# STM32F103C8T6_custom-board.net
KiCad netlist of a schematic drawn in Altium Designer
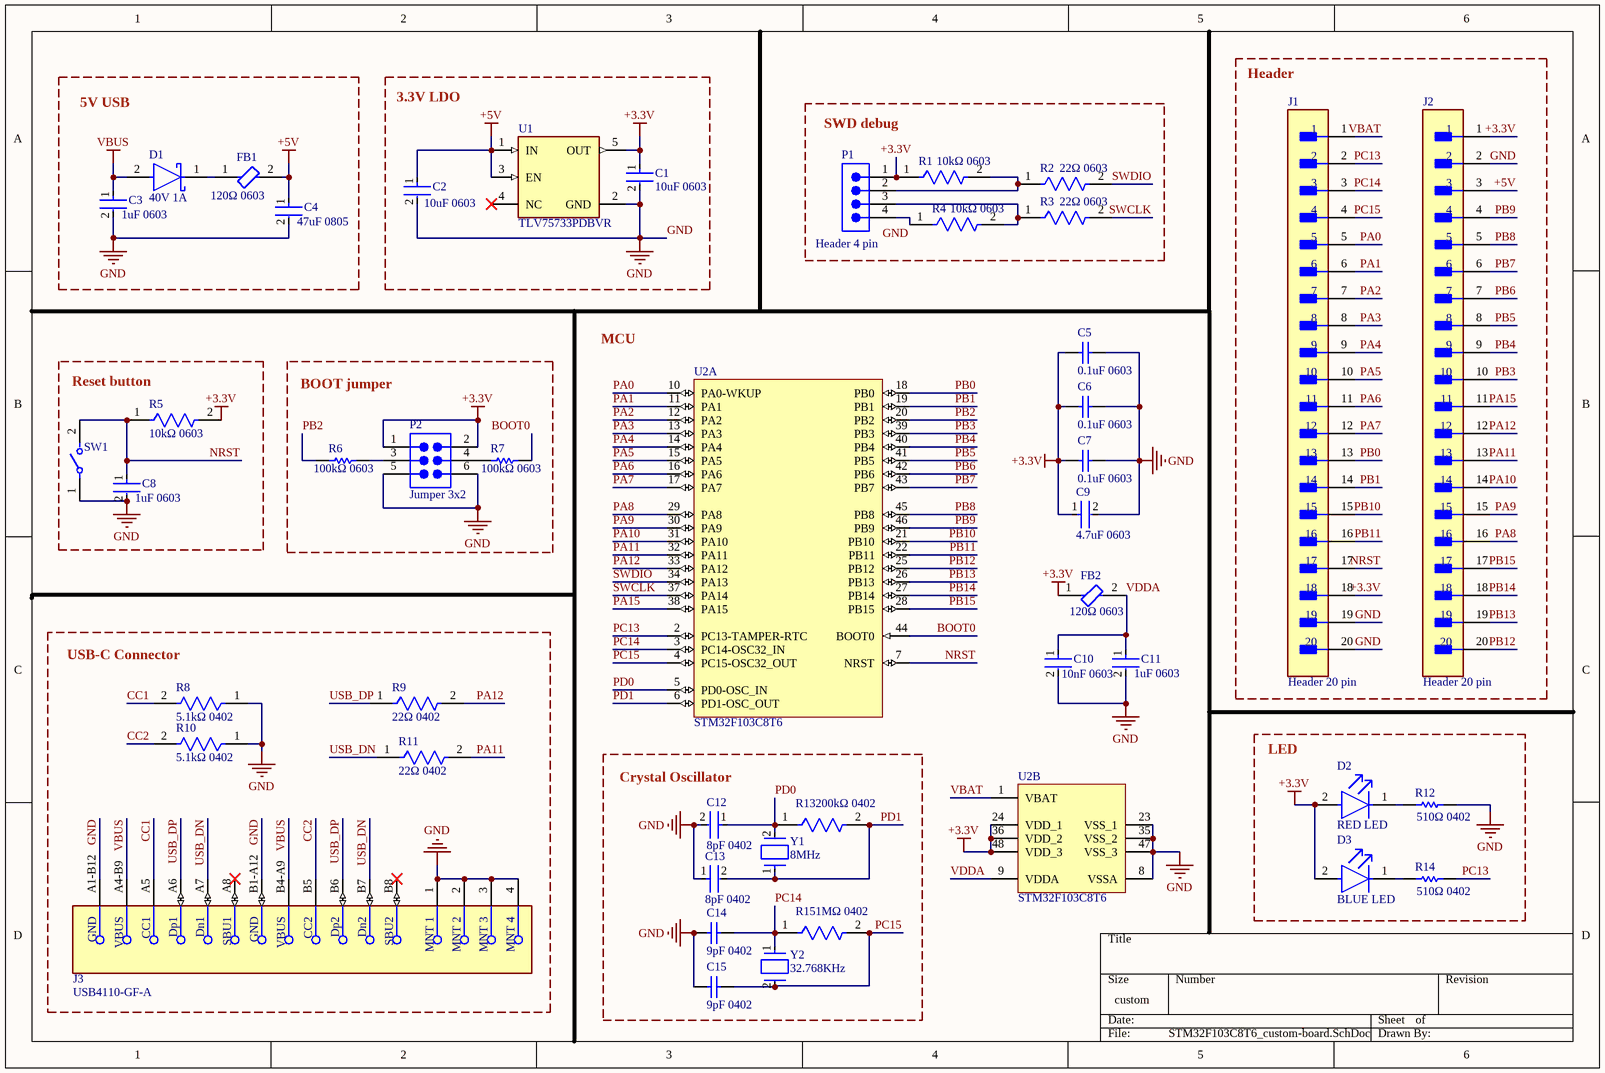
[diagram p0: STM32F103C8T6_custom-board.SchDoc]

(export (version "E")
  (design (tool "Eeschema 10.0.6"))
  (components
    (comp (ref "C1")
      (value "10uF 0603")
      (footprint "FP-CC0603-DC-IPC_A")
      (description "CAP CER 10UF 10V X5R 0603")
      (fields (field (name "TOLERANCE") "10%"))
      (libsource (lib "Altium Content Vault") (part "b4654b650e69147ec39a6b967a45e02"))
    )
    (comp (ref "C2")
      (value "10uF 0603")
      (footprint "FP-CC0603-DC-IPC_A")
      (description "CAP CER 10UF 10V X5R 0603")
      (fields (field (name "TOLERANCE") "10%"))
      (libsource (lib "Altium Content Vault") (part "b4654b650e69147ec39a6b967a45e02"))
    )
    (comp (ref "C3")
      (value "1uF 0603")
      (footprint "FP-VJ0603Y105KXJCW1BC-MFG")
      (description "VJ0603Y105KXJCW1BC Multilayer Ceramic Capacitor, 1 uF, 16 V, ± 10%, X7R, 0603 [1608 Metric]")
      (fields (field (name "TOLERANCE") "10%"))
      (libsource (lib "Altium Content Vault") (part "b4654b650e69147ec39a6b967a45e02"))
    )
    (comp (ref "C4")
      (value "47uF 0805")
      (footprint "FP-C2012-125-0_2-IPC_A")
      (description "Multilayer Ceramic Capacitors 47μF ±20% 10V JB SMD 0805")
      (fields (field (name "TOLERANCE") "20%"))
      (libsource (lib "Altium Content Vault") (part "b4654b650e69147ec39a6b967a45e02"))
    )
    (comp (ref "C5")
      (value "0.1uF 0603")
      (footprint "CAPC1608X95X40ML15T15")
      (fields (field (name "MANUFACTURER") "Vitramon") (field (name "PART NUMBER") "VJ0603Y104KXQCW1BC"))
      (libsource (lib "Altium Content Vault") (part "CAP"))
    )
    (comp (ref "C6")
      (value "0.1uF 0603")
      (footprint "CAPC1608X95X40ML15T15")
      (fields (field (name "MANUFACTURER") "Vitramon") (field (name "PART NUMBER") "VJ0603Y104KXQCW1BC"))
      (libsource (lib "Altium Content Vault") (part "CAP"))
    )
    (comp (ref "C7")
      (value "0.1uF 0603")
      (footprint "CAPC1608X95X40ML15T15")
      (fields (field (name "MANUFACTURER") "Vitramon") (field (name "PART NUMBER") "VJ0603Y104KXQCW1BC"))
      (libsource (lib "Altium Content Vault") (part "CAP"))
    )
    (comp (ref "C8")
      (value "1uF 0603")
      (footprint "FP-VJ0603Y105KXJCW1BC-MFG")
      (description "VJ0603Y105KXJCW1BC Multilayer Ceramic Capacitor, 1 uF, 16 V, ± 10%, X7R, 0603 [1608 Metric]")
      (fields (field (name "TOLERANCE") "10%"))
      (libsource (lib "Altium Content Vault") (part "b4654b650e69147ec39a6b967a45e02"))
    )
    (comp (ref "C9")
      (value "4.7uF 0603")
      (footprint "FP-CC0603-DC-MFG")
      (description "CAP CER 4.7UF 6.3V X7R 0603")
      (fields (field (name "TOLERANCE") "20%"))
      (libsource (lib "Altium Content Vault") (part "11868f565c42a9108669ba33697ecf6"))
    )
    (comp (ref "C10")
      (value "10nF 0603")
      (footprint "FP-C0603C-CF-MFG")
      (description "C0603 10,000 pF X7R 30ppm/°C 5.00% 16 V")
      (fields
        (field (name "MANUFACTURER") "KEMET")
        (field (name "MANUFACTURER PART NUMBER") "C0603C103J4RACAUTO")
      )
      (libsource (lib "Altium Content Vault") (part "b4654b650e69147ec39a6b967a45e02"))
    )
    (comp (ref "C11")
      (value "1uF 0603")
      (footprint "FP-VJ0603Y105KXJCW1BC-MFG")
      (description "VJ0603Y105KXJCW1BC Multilayer Ceramic Capacitor, 1 uF, 16 V, ± 10%, X7R, 0603 [1608 Metric]")
      (fields (field (name "TOLERANCE") "10%"))
      (libsource (lib "Altium Content Vault") (part "b4654b650e69147ec39a6b967a45e02"))
    )
    (comp (ref "C12")
      (value "8pF 0402")
      (footprint "FP-C0402-BB-MFG")
      (description "C0402 8.2 pF C0G 0.5 pF 50 V")
      (fields
        (field (name "OCTOPART") "https://octopart.com/c0402c829d5gacauto-kemet-89441553")
        (field (name "TOLERANCE") "0.5 pF")
      )
      (libsource (lib "Altium Content Vault") (part "b4654b650e69147ec39a6b967a45e02"))
    )
    (comp (ref "C13")
      (value "8pF 0402")
      (footprint "FP-C0402-BB-MFG")
      (description "C0402 8.2 pF C0G 0.5 pF 50 V")
      (fields
        (field (name "OCTOPART") "https://octopart.com/c0402c829d5gacauto-kemet-89441553")
        (field (name "TOLERANCE") "0.5 pF")
      )
      (libsource (lib "Altium Content Vault") (part "b4654b650e69147ec39a6b967a45e02"))
    )
    (comp (ref "C14")
      (value "9pF 0402")
      (footprint "CAPC1005X56X25NL10T15")
      (fields
        (field (name "MANUFACTURER") "AVX Interconnect / Elco")
        (field (name "PART NUMBER") "04023A100DAT2A")
      )
      (libsource (lib "Altium Content Vault") (part "CAP"))
    )
    (comp (ref "C15")
      (value "9pF 0402")
      (footprint "CAPC1005X56X25NL10T15")
      (fields
        (field (name "MANUFACTURER") "AVX Interconnect / Elco")
        (field (name "PART NUMBER") "04023A100DAT2A")
      )
      (libsource (lib "Altium Content Vault") (part "CAP"))
    )
    (comp (ref "D1")
      (value "40V 1A")
      (footprint "FP-SOD123-IPC_A")
      (description "DIODE SCHOTTKY 40V 1A SOD123")
      (libsource (lib "Altium Content Vault") (part "1d6ec82d83fb6aee721767c19dac4b9"))
    )
    (comp (ref "D2")
      (value "RED LED")
      (footprint "FP-SML-LX0603IW-TR-MFG")
      (description "LED RED DIFFUSED SMD")
      (libsource (lib "Altium Content Vault") (part "8706943c75ba83719d021d2fdc84c58"))
    )
    (comp (ref "D3")
      (value "BLUE LED")
      (footprint "FP-LTST-C191TBKT-MFG")
      (description "LED BLUE CLEAR CHIP SMD")
      (libsource (lib "Altium Content Vault") (part "8706943c75ba83719d021d2fdc84c58"))
    )
    (comp (ref "FB1")
      (value "120Ω 0603")
      (footprint "FP-BLM18-0_15-t0_8-MFG")
      (description "Chip Ferrite Bead, 0603, 120Ω @ 100MHz, 0.05Ω, 25%, 2A")
      (libsource (lib "Altium Content Vault") (part "5f30dd21d616792df468990f7003faa"))
    )
    (comp (ref "FB2")
      (value "120Ω 0603")
      (footprint "FP-BLM18-0_15-t0_8-MFG")
      (description "Chip Ferrite Bead, 0603, 120Ω @ 100MHz, 0.05Ω, 25%, 2A")
      (libsource (lib "Altium Content Vault") (part "5f30dd21d616792df468990f7003faa"))
    )
    (comp (ref "J1")
      (value "Header 20 pin")
      (footprint "FP-TSW-120-05-G-S-MFG")
      (description "TSW-120-05-G-S Headers & Wire Housings Classic PCB Header Strips, 0.100 pitch")
      (libsource (lib "Altium Content Vault") (part "aa9a6f52efaac70338c2092749629fc"))
    )
    (comp (ref "J2")
      (value "Header 20 pin")
      (footprint "FP-TSW-120-05-G-S-MFG")
      (description "TSW-120-05-G-S Headers & Wire Housings Classic PCB Header Strips, 0.100 pitch")
      (libsource (lib "Altium Content Vault") (part "aa9a6f52efaac70338c2092749629fc"))
    )
    (comp (ref "J3")
      (value "USB4110-GF-A")
      (footprint "FP-USB4110-GF-A-MFG")
      (description "CONN USB 2.0 TYPE-C R/A SMT")
      (fields
        (field (name "OCTOPART") "https://octopart.com/usb4110-gf-a-gct-103941985")
        (field (name "MANUFACTURER") "GCT")
      )
      (libsource (lib "Altium Content Vault") (part "e23f2b38bb3c3f98e683ebab9ede730"))
    )
    (comp (ref "P1")
      (value "Header 4 pin")
      (footprint "SMTC-TSW-104-08-X-S")
      (description "0.025\" SQ Post Header, Through-hole, Vertical, -55 to 125 degC, 2.54 mm Pitch, 4-Pin, Male, RoHS")
      (fields (field (name "MANUFACTURER") "Samtec") (field (name "PARTNUMBER") "TSW-104-08-G-S"))
      (libsource (lib "Altium Content Vault") (part "SMTC-TSW-104-08-X-S"))
    )
    (comp (ref "P2")
      (value "Jumper 3x2")
      (footprint "SMTC-TSW-103-08-X-D")
      (description "0.025\" SQ Post Header, Through-hole, Vertical, -55 to 125 degC, 2.54 mm Pitch, 6-Pin, Male, RoHS")
      (fields (field (name "MANUFACTURER") "Samtec") (field (name "PARTNUMBER") "TSW-103-08-F-D"))
      (libsource (lib "Altium Content Vault") (part "SMTC-TSW-103-08-X-D"))
    )
    (comp (ref "R1")
      (value "10kΩ 0603")
      (footprint "FP-AC0603-IPC_A")
      (description "RES 10kΩ 5.00% 0.2W 0603")
      (libsource (lib "Altium Content Vault") (part "1029c3af85768c4190bb7ad29bc67b5"))
    )
    (comp (ref "R2")
      (value "22Ω 0603")
      (footprint "FP-RMCF0603-IPC_A")
      (description "22Ω ±5% 0.1W 0603 Thick Film Chip Resistor AEC-Q200 compliant")
      (fields (field (name "TOLERANCE") "5%"))
      (libsource (lib "Altium Content Vault") (part "1029c3af85768c4190bb7ad29bc67b5"))
    )
    (comp (ref "R3")
      (value "22Ω 0603")
      (footprint "FP-RMCF0603-IPC_A")
      (description "22Ω ±5% 0.1W 0603 Thick Film Chip Resistor AEC-Q200 compliant")
      (fields (field (name "TOLERANCE") "5%"))
      (libsource (lib "Altium Content Vault") (part "1029c3af85768c4190bb7ad29bc67b5"))
    )
    (comp (ref "R4")
      (value "10kΩ 0603")
      (footprint "FP-AC0603-IPC_A")
      (description "RES 10kΩ 5.00% 0.2W 0603")
      (libsource (lib "Altium Content Vault") (part "1029c3af85768c4190bb7ad29bc67b5"))
    )
    (comp (ref "R5")
      (value "10kΩ 0603")
      (footprint "FP-AC0603-IPC_A")
      (description "RES 10kΩ 5.00% 0.2W 0603")
      (libsource (lib "Altium Content Vault") (part "1029c3af85768c4190bb7ad29bc67b5"))
    )
    (comp (ref "R6")
      (value "100kΩ 0603")
      (footprint "RESC0603(1608)_N")
      (description "100K 0.1W 1% 0603 (1608 Metric)  SMD")
      (fields (field (name "POWER") "0.1 W") (field (name "TOLERANCE") "1 %"))
      (libsource (lib "Altium Content Vault") (part "RES"))
    )
    (comp (ref "R7")
      (value "100kΩ 0603")
      (footprint "RESC0603(1608)_N")
      (description "100K 0.1W 1% 0603 (1608 Metric)  SMD")
      (fields (field (name "POWER") "0.1 W") (field (name "TOLERANCE") "1 %"))
      (libsource (lib "Altium Content Vault") (part "RES"))
    )
    (comp (ref "R8")
      (value "5.1kΩ 0402")
      (footprint "FP-RN73R1E-IPC_C")
      (description "5.1kΩ ±1% 0.063W, 1/16W Chip Resistor 0402 (1005 Metric) Moisture Resistant Thin Film")
      (libsource (lib "Altium Content Vault") (part "1029c3af85768c4190bb7ad29bc67b5"))
    )
    (comp (ref "R9")
      (value "22Ω 0402")
      (footprint "FP-RMCF0402-MFG")
      (description "22Ω ±1% 0.063W 0402 Thick Film Chip Resistor AEC-Q200 compliant")
      (fields (field (name "TOLERANCE") "1%"))
      (libsource (lib "Altium Content Vault") (part "1029c3af85768c4190bb7ad29bc67b5"))
    )
    (comp (ref "R10")
      (value "5.1kΩ 0402")
      (footprint "FP-RN73R1E-IPC_C")
      (description "5.1kΩ ±1% 0.063W, 1/16W Chip Resistor 0402 (1005 Metric) Moisture Resistant Thin Film")
      (libsource (lib "Altium Content Vault") (part "1029c3af85768c4190bb7ad29bc67b5"))
    )
    (comp (ref "R11")
      (value "22Ω 0402")
      (footprint "FP-RMCF0402-MFG")
      (description "22Ω ±1% 0.063W 0402 Thick Film Chip Resistor AEC-Q200 compliant")
      (fields (field (name "TOLERANCE") "1%"))
      (libsource (lib "Altium Content Vault") (part "1029c3af85768c4190bb7ad29bc67b5"))
    )
    (comp (ref "R12")
      (value "510Ω 0402")
      (footprint "RESC1005X40X25LL05T05")
      (fields (field (name "MANUFACTURER") "Vishay Dale") (field (name "PART NUMBER") "CRCW0402510RJNTD"))
      (libsource (lib "Altium Content Vault") (part "RES"))
    )
    (comp (ref "R13")
      (value "200kΩ 0402")
      (footprint "FP-CRCW0402-Pe3-MFG")
      (description "RES Thick Film, 200kΩ, 1%, 0.063W, 50ppm/°C, 0402")
      (fields (field (name "TOLERANCE") "1%"))
      (libsource (lib "Altium Content Vault") (part "1029c3af85768c4190bb7ad29bc67b5"))
    )
    (comp (ref "R14")
      (value "510Ω 0402")
      (footprint "RESC1005X40X25LL05T05")
      (fields (field (name "MANUFACTURER") "Vishay Dale") (field (name "PART NUMBER") "CRCW0402510RJNTD"))
      (libsource (lib "Altium Content Vault") (part "RES"))
    )
    (comp (ref "R15")
      (value "1MΩ 0402")
      (footprint "FP-MCS0402-MFG")
      (description "RES SMD 1.2K OHM 1% 1/10W 0402")
      (fields (field (name "TOLERANCE") "0.1%"))
      (libsource (lib "Altium Content Vault") (part "1029c3af85768c4190bb7ad29bc67b5"))
    )
    (comp (ref "SW1")
      (value "~")
      (footprint "FP-PTS635SK25SM-MFG")
      (description "SWITCH TACTILE SPST-NO 0.05A 12V")
      (fields
        (field (name "OCTOPART") "https://octopart.com/pts635sk25sm-c%26k+components-8206497")
        (field (name "MANUFACTURER") "C&K Components")
      )
      (libsource (lib "Altium Content Vault") (part "bb27bde45df87f1f469753f287ef5ae"))
    )
    (comp (ref "U1")
      (value "TLV75733PDBVR")
      (footprint "FP-DBV0005A-MFG")
      (description "IC REG LINEAR 3.3V 1A SOT23-5")
      (fields
        (field (name "MANUFACTURER") "Texas Instruments")
        (field (name "OCTOPART") "https://octopart.com/tlv75733pdbvr-texas+instruments-91437073")
      )
      (libsource (lib "Altium Content Vault") (part "0cbbc1df71e5372cce39b1d408f1f92"))
    )
    (comp (ref "U2")
      (value "STM32F103C8T6")
      (footprint "STM-LQFP48_L")
      (libsource (lib "Altium Content Vault") (part "MC-ARM-STM32F103X8_B-SQ48"))
    )
    (comp (ref "Y1")
      (value "8MHz")
      (footprint "FP-ABM7-MFG")
      (description "Crystal 8MHz ±20ppm 8pF SMD-2 6mm x 3.5mm")
      (libsource (lib "Altium Content Vault") (part "c23a69dc6c9e2f18f2079038eb95dd1"))
    )
    (comp (ref "Y2")
      (value "32.768KHz")
      (footprint "FP-ABS07AIG-MFG")
      (description "Crystal 32.768kHz ±20ppm (Tol) 9pF FUND 70kΩ Automotive 2-Pin Mini-CSMD T/R")
      (libsource (lib "Altium Content Vault") (part "c23a69dc6c9e2f18f2079038eb95dd1"))
    )
  )
  (nets
    (net (code "1") (name "+3.3V") (class "Default")
      (node (ref "C1") (pin "1") (pinfunction "1_1") (pintype "passive"))
      (node (ref "C5") (pin "2") (pinfunction "2_2") (pintype "passive"))
      (node (ref "C6") (pin "2") (pinfunction "2_2") (pintype "passive"))
      (node (ref "C7") (pin "2") (pinfunction "2_2") (pintype "passive"))
      (node (ref "C9") (pin "1") (pinfunction "1_1") (pintype "passive"))
      (node (ref "D2") (pin "2") (pinfunction "A_2") (pintype "passive"))
      (node (ref "D3") (pin "2") (pinfunction "A_2") (pintype "passive"))
      (node (ref "FB2") (pin "1") (pinfunction "1_1") (pintype "passive"))
      (node (ref "J1") (pin "18") (pinfunction "18_18") (pintype "passive"))
      (node (ref "J2") (pin "1") (pinfunction "1_1") (pintype "passive"))
      (node (ref "P1") (pin "1") (pinfunction "1_1") (pintype "passive"))
      (node (ref "P2") (pin "1") (pinfunction "1_1") (pintype "passive"))
      (node (ref "P2") (pin "2") (pinfunction "2_2") (pintype "passive"))
      (node (ref "R1") (pin "1") (pinfunction "1_1") (pintype "passive"))
      (node (ref "R5") (pin "2") (pinfunction "2_2") (pintype "passive"))
      (node (ref "U1") (pin "5") (pinfunction "OUT_5") (pintype "output"))
      (node (ref "U2") (pin "24") (pinfunction "VDD_1_24") (pintype "power_in"))
      (node (ref "U2") (pin "36") (pinfunction "VDD_2_36") (pintype "power_in"))
      (node (ref "U2") (pin "48") (pinfunction "VDD_3_48") (pintype "power_in"))
    )
    (net (code "2") (name "+5V") (class "Default")
      (node (ref "C2") (pin "1") (pinfunction "1_1") (pintype "passive"))
      (node (ref "C4") (pin "1") (pinfunction "1_1") (pintype "passive"))
      (node (ref "FB1") (pin "2") (pinfunction "2_2") (pintype "passive"))
      (node (ref "J2") (pin "3") (pinfunction "3_3") (pintype "passive"))
      (node (ref "U1") (pin "1") (pinfunction "IN_1") (pintype "input"))
      (node (ref "U1") (pin "3") (pinfunction "EN_3") (pintype "input"))
    )
    (net (code "3") (name "/BOOT0") (class "Default")
      (node (ref "R7") (pin "2") (pinfunction "2_2") (pintype "passive"))
      (node (ref "U2") (pin "44") (pinfunction "BOOT0_44") (pintype "input"))
    )
    (net (code "4") (name "/CC1") (class "Default")
      (node (ref "J3") (pin "A5") (pinfunction "CC1_A5") (pintype "power_in"))
      (node (ref "R8") (pin "2") (pinfunction "2_2") (pintype "passive"))
    )
    (net (code "5") (name "/CC2") (class "Default")
      (node (ref "J3") (pin "B5") (pinfunction "CC2_B5") (pintype "power_in"))
      (node (ref "R10") (pin "2") (pinfunction "2_2") (pintype "passive"))
    )
    (net (code "6") (name "/NRST") (class "Default")
      (node (ref "C8") (pin "1") (pinfunction "1_1") (pintype "passive"))
      (node (ref "J1") (pin "17") (pinfunction "17_17") (pintype "passive"))
      (node (ref "R5") (pin "1") (pinfunction "1_1") (pintype "passive"))
      (node (ref "SW1") (pin "2") (pinfunction "2_2") (pintype "passive"))
      (node (ref "U2") (pin "7") (pinfunction "NRST_7") (pintype "bidirectional"))
    )
    (net (code "7") (name "/PA0") (class "Default")
      (node (ref "J1") (pin "5") (pinfunction "5_5") (pintype "passive"))
      (node (ref "U2") (pin "10") (pinfunction "PA0-WKUP_10") (pintype "bidirectional"))
    )
    (net (code "8") (name "/PA1") (class "Default")
      (node (ref "J1") (pin "6") (pinfunction "6_6") (pintype "passive"))
      (node (ref "U2") (pin "11") (pinfunction "PA1_11") (pintype "bidirectional"))
    )
    (net (code "9") (name "/PA2") (class "Default")
      (node (ref "J1") (pin "7") (pinfunction "7_7") (pintype "passive"))
      (node (ref "U2") (pin "12") (pinfunction "PA2_12") (pintype "bidirectional"))
    )
    (net (code "10") (name "/PA3") (class "Default")
      (node (ref "J1") (pin "8") (pinfunction "8_8") (pintype "passive"))
      (node (ref "U2") (pin "13") (pinfunction "PA3_13") (pintype "bidirectional"))
    )
    (net (code "11") (name "/PA4") (class "Default")
      (node (ref "J1") (pin "9") (pinfunction "9_9") (pintype "passive"))
      (node (ref "U2") (pin "14") (pinfunction "PA4_14") (pintype "bidirectional"))
    )
    (net (code "12") (name "/PA5") (class "Default")
      (node (ref "J1") (pin "10") (pinfunction "10_10") (pintype "passive"))
      (node (ref "U2") (pin "15") (pinfunction "PA5_15") (pintype "bidirectional"))
    )
    (net (code "13") (name "/PA6") (class "Default")
      (node (ref "J1") (pin "11") (pinfunction "11_11") (pintype "passive"))
      (node (ref "U2") (pin "16") (pinfunction "PA6_16") (pintype "bidirectional"))
    )
    (net (code "14") (name "/PA7") (class "Default")
      (node (ref "J1") (pin "12") (pinfunction "12_12") (pintype "passive"))
      (node (ref "U2") (pin "17") (pinfunction "PA7_17") (pintype "bidirectional"))
    )
    (net (code "15") (name "/PA8") (class "Default")
      (node (ref "J2") (pin "16") (pinfunction "16_16") (pintype "passive"))
      (node (ref "U2") (pin "29") (pinfunction "PA8_29") (pintype "bidirectional"))
    )
    (net (code "16") (name "/PA9") (class "Default")
      (node (ref "J2") (pin "15") (pinfunction "15_15") (pintype "passive"))
      (node (ref "U2") (pin "30") (pinfunction "PA9_30") (pintype "bidirectional"))
    )
    (net (code "17") (name "/PA10") (class "Default")
      (node (ref "J2") (pin "14") (pinfunction "14_14") (pintype "passive"))
      (node (ref "U2") (pin "31") (pinfunction "PA10_31") (pintype "bidirectional"))
    )
    (net (code "18") (name "/PA11") (class "Default")
      (node (ref "J2") (pin "13") (pinfunction "13_13") (pintype "passive"))
      (node (ref "R11") (pin "2") (pinfunction "2_2") (pintype "passive"))
      (node (ref "U2") (pin "32") (pinfunction "PA11_32") (pintype "bidirectional"))
    )
    (net (code "19") (name "/PA12") (class "Default")
      (node (ref "J2") (pin "12") (pinfunction "12_12") (pintype "passive"))
      (node (ref "R9") (pin "2") (pinfunction "2_2") (pintype "passive"))
      (node (ref "U2") (pin "33") (pinfunction "PA12_33") (pintype "bidirectional"))
    )
    (net (code "20") (name "/PA15") (class "Default")
      (node (ref "J2") (pin "11") (pinfunction "11_11") (pintype "passive"))
      (node (ref "U2") (pin "38") (pinfunction "PA15_38") (pintype "bidirectional"))
    )
    (net (code "21") (name "/PB0") (class "Default")
      (node (ref "J1") (pin "13") (pinfunction "13_13") (pintype "passive"))
      (node (ref "U2") (pin "18") (pinfunction "PB0_18") (pintype "bidirectional"))
    )
    (net (code "22") (name "/PB1") (class "Default")
      (node (ref "J1") (pin "14") (pinfunction "14_14") (pintype "passive"))
      (node (ref "U2") (pin "19") (pinfunction "PB1_19") (pintype "bidirectional"))
    )
    (net (code "23") (name "/PB2") (class "Default")
      (node (ref "R6") (pin "1") (pinfunction "1_1") (pintype "passive"))
      (node (ref "U2") (pin "20") (pinfunction "PB2_20") (pintype "bidirectional"))
    )
    (net (code "24") (name "/PB3") (class "Default")
      (node (ref "J2") (pin "10") (pinfunction "10_10") (pintype "passive"))
      (node (ref "U2") (pin "39") (pinfunction "PB3_39") (pintype "bidirectional"))
    )
    (net (code "25") (name "/PB4") (class "Default")
      (node (ref "J2") (pin "9") (pinfunction "9_9") (pintype "passive"))
      (node (ref "U2") (pin "40") (pinfunction "PB4_40") (pintype "bidirectional"))
    )
    (net (code "26") (name "/PB5") (class "Default")
      (node (ref "J2") (pin "8") (pinfunction "8_8") (pintype "passive"))
      (node (ref "U2") (pin "41") (pinfunction "PB5_41") (pintype "bidirectional"))
    )
    (net (code "27") (name "/PB6") (class "Default")
      (node (ref "J2") (pin "7") (pinfunction "7_7") (pintype "passive"))
      (node (ref "U2") (pin "42") (pinfunction "PB6_42") (pintype "bidirectional"))
    )
    (net (code "28") (name "/PB7") (class "Default")
      (node (ref "J2") (pin "6") (pinfunction "6_6") (pintype "passive"))
      (node (ref "U2") (pin "43") (pinfunction "PB7_43") (pintype "bidirectional"))
    )
    (net (code "29") (name "/PB8") (class "Default")
      (node (ref "J2") (pin "5") (pinfunction "5_5") (pintype "passive"))
      (node (ref "U2") (pin "45") (pinfunction "PB8_45") (pintype "bidirectional"))
    )
    (net (code "30") (name "/PB9") (class "Default")
      (node (ref "J2") (pin "4") (pinfunction "4_4") (pintype "passive"))
      (node (ref "U2") (pin "46") (pinfunction "PB9_46") (pintype "bidirectional"))
    )
    (net (code "31") (name "/PB10") (class "Default")
      (node (ref "J1") (pin "15") (pinfunction "15_15") (pintype "passive"))
      (node (ref "U2") (pin "21") (pinfunction "PB10_21") (pintype "bidirectional"))
    )
    (net (code "32") (name "/PB11") (class "Default")
      (node (ref "J1") (pin "16") (pinfunction "16_16") (pintype "passive"))
      (node (ref "U2") (pin "22") (pinfunction "PB11_22") (pintype "bidirectional"))
    )
    (net (code "33") (name "/PB12") (class "Default")
      (node (ref "J2") (pin "20") (pinfunction "20_20") (pintype "passive"))
      (node (ref "U2") (pin "25") (pinfunction "PB12_25") (pintype "bidirectional"))
    )
    (net (code "34") (name "/PB13") (class "Default")
      (node (ref "J2") (pin "19") (pinfunction "19_19") (pintype "passive"))
      (node (ref "U2") (pin "26") (pinfunction "PB13_26") (pintype "bidirectional"))
    )
    (net (code "35") (name "/PB14") (class "Default")
      (node (ref "J2") (pin "18") (pinfunction "18_18") (pintype "passive"))
      (node (ref "U2") (pin "27") (pinfunction "PB14_27") (pintype "bidirectional"))
    )
    (net (code "36") (name "/PB15") (class "Default")
      (node (ref "J2") (pin "17") (pinfunction "17_17") (pintype "passive"))
      (node (ref "U2") (pin "28") (pinfunction "PB15_28") (pintype "bidirectional"))
    )
    (net (code "37") (name "/PC13") (class "Default")
      (node (ref "J1") (pin "2") (pinfunction "2_2") (pintype "passive"))
      (node (ref "R14") (pin "2") (pinfunction "2_2") (pintype "passive"))
      (node (ref "U2") (pin "2") (pinfunction "PC13-TAMPER-RTC_2") (pintype "bidirectional"))
    )
    (net (code "38") (name "/PC14") (class "Default")
      (node (ref "C14") (pin "2") (pinfunction "2_2") (pintype "passive"))
      (node (ref "J1") (pin "3") (pinfunction "3_3") (pintype "passive"))
      (node (ref "R15") (pin "1") (pinfunction "1_1") (pintype "passive"))
      (node (ref "U2") (pin "3") (pinfunction "PC14-OSC32_IN_3") (pintype "bidirectional"))
      (node (ref "Y2") (pin "1") (pinfunction "1_1") (pintype "passive"))
    )
    (net (code "39") (name "/PC15") (class "Default")
      (node (ref "C15") (pin "2") (pinfunction "2_2") (pintype "passive"))
      (node (ref "J1") (pin "4") (pinfunction "4_4") (pintype "passive"))
      (node (ref "R15") (pin "2") (pinfunction "2_2") (pintype "passive"))
      (node (ref "U2") (pin "4") (pinfunction "PC15-OSC32_OUT_4") (pintype "bidirectional"))
      (node (ref "Y2") (pin "2") (pinfunction "2_2") (pintype "passive"))
    )
    (net (code "40") (name "/PD0") (class "Default")
      (node (ref "C12") (pin "1") (pinfunction "1_1") (pintype "passive"))
      (node (ref "R13") (pin "1") (pinfunction "1_1") (pintype "passive"))
      (node (ref "U2") (pin "5") (pinfunction "PD0-OSC_IN_5") (pintype "bidirectional"))
      (node (ref "Y1") (pin "2") (pinfunction "2_2") (pintype "passive"))
    )
    (net (code "41") (name "/PD1") (class "Default")
      (node (ref "C13") (pin "2") (pinfunction "2_2") (pintype "passive"))
      (node (ref "R13") (pin "2") (pinfunction "2_2") (pintype "passive"))
      (node (ref "U2") (pin "6") (pinfunction "PD1-OSC_OUT_6") (pintype "bidirectional"))
      (node (ref "Y1") (pin "1") (pinfunction "1_1") (pintype "passive"))
    )
    (net (code "42") (name "/SWCLK") (class "Default")
      (node (ref "R3") (pin "2") (pinfunction "2_2") (pintype "passive"))
      (node (ref "U2") (pin "37") (pinfunction "PA14_37") (pintype "bidirectional"))
    )
    (net (code "43") (name "/SWDIO") (class "Default")
      (node (ref "R2") (pin "2") (pinfunction "2_2") (pintype "passive"))
      (node (ref "U2") (pin "34") (pinfunction "PA13_34") (pintype "bidirectional"))
    )
    (net (code "44") (name "/USB_DN") (class "Default")
      (node (ref "J3") (pin "A7") (pinfunction "Dn1_A7") (pintype "bidirectional"))
      (node (ref "J3") (pin "B7") (pinfunction "Dn2_B7") (pintype "bidirectional"))
      (node (ref "R11") (pin "1") (pinfunction "1_1") (pintype "passive"))
    )
    (net (code "45") (name "/USB_DP") (class "Default")
      (node (ref "J3") (pin "A6") (pinfunction "Dp1_A6") (pintype "bidirectional"))
      (node (ref "J3") (pin "B6") (pinfunction "Dp2_B6") (pintype "bidirectional"))
      (node (ref "R9") (pin "1") (pinfunction "1_1") (pintype "passive"))
    )
    (net (code "46") (name "/VBAT") (class "Default")
      (node (ref "J1") (pin "1") (pinfunction "1_1") (pintype "passive"))
      (node (ref "U2") (pin "1") (pinfunction "VBAT_1") (pintype "power_in"))
    )
    (net (code "47") (name "/VDDA") (class "Default")
      (node (ref "C10") (pin "1") (pinfunction "1_1") (pintype "passive"))
      (node (ref "C11") (pin "1") (pinfunction "1_1") (pintype "passive"))
      (node (ref "FB2") (pin "2") (pinfunction "2_2") (pintype "passive"))
      (node (ref "U2") (pin "9") (pinfunction "VDDA_9") (pintype "power_in"))
    )
    (net (code "48") (name "GND") (class "Default")
      (node (ref "C1") (pin "2") (pinfunction "2_2") (pintype "passive"))
      (node (ref "C10") (pin "2") (pinfunction "2_2") (pintype "passive"))
      (node (ref "C11") (pin "2") (pinfunction "2_2") (pintype "passive"))
      (node (ref "C12") (pin "2") (pinfunction "2_2") (pintype "passive"))
      (node (ref "C13") (pin "1") (pinfunction "1_1") (pintype "passive"))
      (node (ref "C14") (pin "1") (pinfunction "1_1") (pintype "passive"))
      (node (ref "C15") (pin "1") (pinfunction "1_1") (pintype "passive"))
      (node (ref "C2") (pin "2") (pinfunction "2_2") (pintype "passive"))
      (node (ref "C3") (pin "2") (pinfunction "2_2") (pintype "passive"))
      (node (ref "C4") (pin "2") (pinfunction "2_2") (pintype "passive"))
      (node (ref "C5") (pin "1") (pinfunction "1_1") (pintype "passive"))
      (node (ref "C6") (pin "1") (pinfunction "1_1") (pintype "passive"))
      (node (ref "C7") (pin "1") (pinfunction "1_1") (pintype "passive"))
      (node (ref "C8") (pin "2") (pinfunction "2_2") (pintype "passive"))
      (node (ref "C9") (pin "2") (pinfunction "2_2") (pintype "passive"))
      (node (ref "J1") (pin "19") (pinfunction "19_19") (pintype "passive"))
      (node (ref "J1") (pin "20") (pinfunction "20_20") (pintype "passive"))
      (node (ref "J2") (pin "2") (pinfunction "2_2") (pintype "passive"))
      (node (ref "J3") (pin "1") (pinfunction "MNT_1_1") (pintype "passive"))
      (node (ref "J3") (pin "2") (pinfunction "MNT_2_2") (pintype "passive"))
      (node (ref "J3") (pin "3") (pinfunction "MNT_3_3") (pintype "passive"))
      (node (ref "J3") (pin "4") (pinfunction "MNT_4_4") (pintype "passive"))
      (node (ref "J3") (pin "A1-B12") (pinfunction "GND_A1-B12") (pintype "passive"))
      (node (ref "J3") (pin "B1-A12") (pinfunction "GND_B1-A12") (pintype "bidirectional"))
      (node (ref "P1") (pin "4") (pinfunction "4_4") (pintype "passive"))
      (node (ref "P2") (pin "5") (pinfunction "5_5") (pintype "passive"))
      (node (ref "P2") (pin "6") (pinfunction "6_6") (pintype "passive"))
      (node (ref "R10") (pin "1") (pinfunction "1_1") (pintype "passive"))
      (node (ref "R12") (pin "2") (pinfunction "2_2") (pintype "passive"))
      (node (ref "R4") (pin "1") (pinfunction "1_1") (pintype "passive"))
      (node (ref "R8") (pin "1") (pinfunction "1_1") (pintype "passive"))
      (node (ref "SW1") (pin "1") (pinfunction "1_1") (pintype "passive"))
      (node (ref "U1") (pin "2") (pinfunction "GND_2") (pintype "power_in"))
      (node (ref "U2") (pin "23") (pinfunction "VSS_1_23") (pintype "power_in"))
      (node (ref "U2") (pin "35") (pinfunction "VSS_2_35") (pintype "power_in"))
      (node (ref "U2") (pin "47") (pinfunction "VSS_3_47") (pintype "power_in"))
      (node (ref "U2") (pin "8") (pinfunction "VSSA_8") (pintype "power_in"))
    )
    (net (code "49") (name "Net-(D1-C)") (class "Default")
      (node (ref "D1") (pin "1") (pinfunction "C_1") (pintype "passive"))
      (node (ref "FB1") (pin "1") (pinfunction "1_1") (pintype "passive"))
    )
    (net (code "50") (name "Net-(D2-C)") (class "Default")
      (node (ref "D2") (pin "1") (pinfunction "C_1") (pintype "passive"))
      (node (ref "R12") (pin "1") (pinfunction "1_1") (pintype "passive"))
    )
    (net (code "51") (name "Net-(D3-C)") (class "Default")
      (node (ref "D3") (pin "1") (pinfunction "C_1") (pintype "passive"))
      (node (ref "R14") (pin "1") (pinfunction "1_1") (pintype "passive"))
    )
    (net (code "52") (name "Net-(P1-Pad2)") (class "Default")
      (node (ref "P1") (pin "2") (pinfunction "2_2") (pintype "passive"))
      (node (ref "R1") (pin "2") (pinfunction "2_2") (pintype "passive"))
      (node (ref "R2") (pin "1") (pinfunction "1_1") (pintype "passive"))
    )
    (net (code "53") (name "Net-(P1-Pad3)") (class "Default")
      (node (ref "P1") (pin "3") (pinfunction "3_3") (pintype "passive"))
      (node (ref "R3") (pin "1") (pinfunction "1_1") (pintype "passive"))
      (node (ref "R4") (pin "2") (pinfunction "2_2") (pintype "passive"))
    )
    (net (code "54") (name "Net-(P2-Pad3)") (class "Default")
      (node (ref "P2") (pin "3") (pinfunction "3_3") (pintype "passive"))
      (node (ref "R6") (pin "2") (pinfunction "2_2") (pintype "passive"))
    )
    (net (code "55") (name "Net-(P2-Pad4)") (class "Default")
      (node (ref "P2") (pin "4") (pinfunction "4_4") (pintype "passive"))
      (node (ref "R7") (pin "1") (pinfunction "1_1") (pintype "passive"))
    )
    (net (code "56") (name "VBUS") (class "Default")
      (node (ref "C3") (pin "1") (pinfunction "1_1") (pintype "passive"))
      (node (ref "D1") (pin "2") (pinfunction "A_2") (pintype "passive"))
      (node (ref "J3") (pin "A4-B9") (pinfunction "VBUS_A4-B9") (pintype "power_in"))
      (node (ref "J3") (pin "B4-A9") (pinfunction "VBUS_B4-A9") (pintype "power_in"))
    )
    (net (code "57") (name "unconnected-(J3-SBU1-PadA8)") (class "Default")
      (node (ref "J3") (pin "A8") (pinfunction "SBU1_A8") (pintype "bidirectional+no_connect"))
    )
    (net (code "58") (name "unconnected-(J3-SBU2-PadB8)") (class "Default")
      (node (ref "J3") (pin "B8") (pinfunction "SBU2_B8") (pintype "bidirectional+no_connect"))
    )
    (net (code "59") (name "unconnected-(U1-NC-Pad4)") (class "Default")
      (node (ref "U1") (pin "4") (pinfunction "NC_4") (pintype "passive+no_connect"))
    )
  )
)
